# AMU-S11-V00-ContactorInterface.net
KiCad netlist of a schematic drawn in Altium Designer
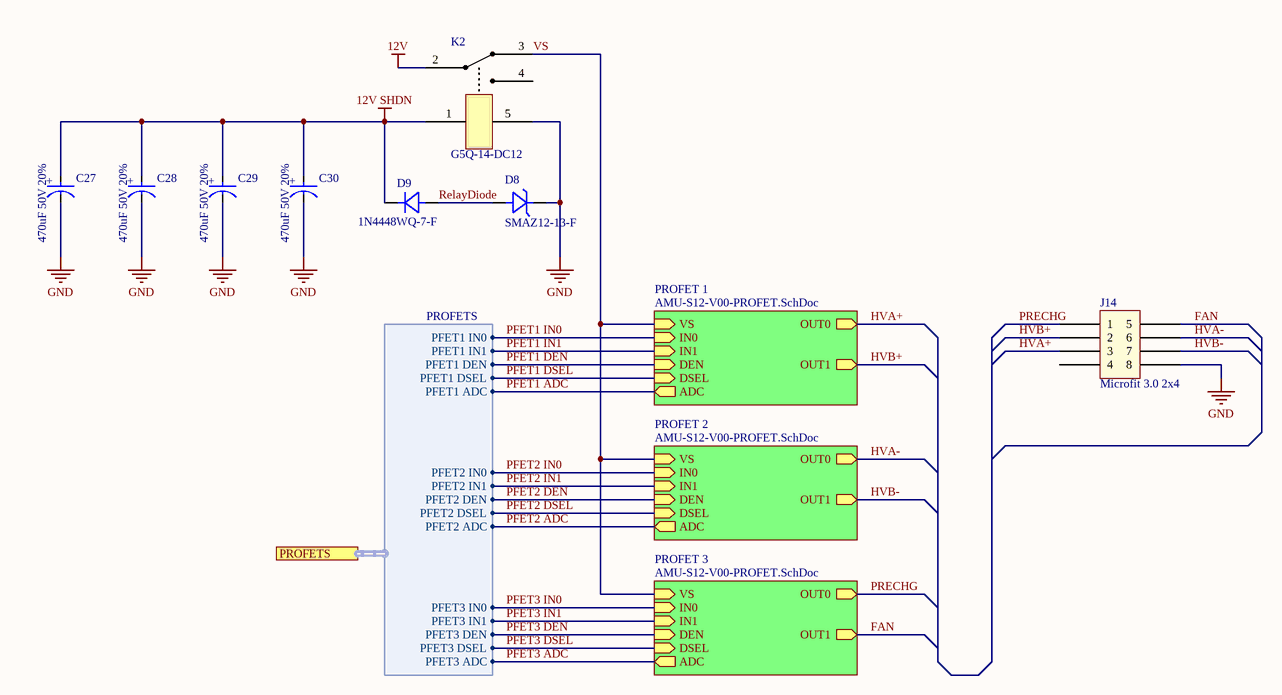
[diagram p0: AMU-S11-V00-ContactorInterface.SchDoc]

(export (version "E")
  (design (tool "Eeschema 10.0.6"))
  (components
    (comp (ref "C27")
      (value "470uF 50V 20%")
      (footprint "CAP_ALU_TH")
      (description "470µF 50V Aluminum Electrolytic Capacitors Radial, Can  5000 Hrs @ 105°C")
      (libsource (lib "StandardCapacitors") (part "470uF 50V 20% Alum E-CAP"))
    )
    (comp (ref "C28")
      (value "470uF 50V 20%")
      (footprint "CAP_ALU_TH")
      (description "470µF 50V Aluminum Electrolytic Capacitors Radial, Can  5000 Hrs @ 105°C")
      (libsource (lib "StandardCapacitors") (part "470uF 50V 20% Alum E-CAP"))
    )
    (comp (ref "C29")
      (value "470uF 50V 20%")
      (footprint "CAP_ALU_TH")
      (description "470µF 50V Aluminum Electrolytic Capacitors Radial, Can  5000 Hrs @ 105°C")
      (libsource (lib "StandardCapacitors") (part "470uF 50V 20% Alum E-CAP"))
    )
    (comp (ref "C30")
      (value "470uF 50V 20%")
      (footprint "CAP_ALU_TH")
      (description "470µF 50V Aluminum Electrolytic Capacitors Radial, Can  5000 Hrs @ 105°C")
      (libsource (lib "StandardCapacitors") (part "470uF 50V 20% Alum E-CAP"))
    )
    (comp (ref "D8")
      (value "SMAZ12-13-F")
      (footprint "SMA")
      (description "Zener Diode 12V 1W ±5% Surface Mount SMA")
      (fields (field (name "MANUFACTURER") "ON Semiconductor") (field (name "MPN") "MM3Z56VB"))
      (libsource (lib "QUTMS_DiodeLibrary") (part "SMAZ12-13-F"))
    )
    (comp (ref "D9")
      (value "1N4448WQ-7-F")
      (footprint "SMA")
      (description "Diode, SMD, 75V, 5%, 250mA, SOD123")
      (fields
        (field (name "MANUFACTURER") "ON Semiconductor / Fairchild")
        (field (name "MANUFACTURER PART NUMBER") "1N914BWS")
      )
      (libsource (lib "QUTMS_DiodeLibrary") (part "1N4448WQ-7-F"))
    )
    (comp (ref "J14")
      (value "Microfit 3.0 2x4")
      (footprint "Microfit_2X4_R_TH")
      (libsource (lib "QUTMS_MicrofitLibrary") (part "Microfit_2x4"))
    )
    (comp (ref "K2")
      (value "G5Q-14-DC12")
      (footprint "G5Q-14")
      (description "General Purpose Relay SPDT (1 Form C) 12VDC Coil Through Hole, 12V, 16A")
      (libsource (lib "QUTMS_RelayLibrary") (part "G5Q-14-DC12"))
    )
  )
  (nets
    (net (code "2") (name "/FAN") (class "Default")
      (node (ref "J14") (pin "5") (pinfunction "5_5") (pintype "passive"))
    )
    (net (code "3") (name "/HVA+") (class "Default")
      (node (ref "J14") (pin "3") (pinfunction "3_3") (pintype "passive"))
    )
    (net (code "4") (name "/HVA-") (class "Default")
      (node (ref "J14") (pin "6") (pinfunction "6_6") (pintype "passive"))
    )
    (net (code "5") (name "/HVB+") (class "Default")
      (node (ref "J14") (pin "2") (pinfunction "2_2") (pintype "passive"))
    )
    (net (code "6") (name "/HVB-") (class "Default")
      (node (ref "J14") (pin "7") (pinfunction "7_7") (pintype "passive"))
    )
    (net (code "22") (name "/PRECHG") (class "Default")
      (node (ref "J14") (pin "1") (pinfunction "1_1") (pintype "passive"))
    )
    (net (code "23") (name "/RelayDiode") (class "Default")
      (node (ref "D8") (pin "A") (pinfunction "Anode_A") (pintype "passive"))
      (node (ref "D9") (pin "A") (pinfunction "Anode_A") (pintype "passive"))
    )
    (net (code "24") (name "/VS") (class "Default")
      (node (ref "K2") (pin "3") (pinfunction "3_3") (pintype "passive"))
    )
    (net (code "26") (name "12V") (class "Default")
      (node (ref "K2") (pin "2") (pinfunction "2_2") (pintype "passive"))
    )
    (net (code "27") (name "12V SHDN") (class "Default")
      (node (ref "C27") (pin "A") (pinfunction "A_A") (pintype "passive"))
      (node (ref "C28") (pin "A") (pinfunction "A_A") (pintype "passive"))
      (node (ref "C29") (pin "A") (pinfunction "A_A") (pintype "passive"))
      (node (ref "C30") (pin "A") (pinfunction "A_A") (pintype "passive"))
      (node (ref "D9") (pin "K") (pinfunction "Cathode_K") (pintype "passive"))
      (node (ref "K2") (pin "1") (pinfunction "1_1") (pintype "passive"))
    )
    (net (code "28") (name "GND") (class "Default")
      (node (ref "C27") (pin "K") (pinfunction "K_K") (pintype "passive"))
      (node (ref "C28") (pin "K") (pinfunction "K_K") (pintype "passive"))
      (node (ref "C29") (pin "K") (pinfunction "K_K") (pintype "passive"))
      (node (ref "C30") (pin "K") (pinfunction "K_K") (pintype "passive"))
      (node (ref "D8") (pin "K") (pinfunction "Cathode_K") (pintype "passive"))
      (node (ref "J14") (pin "8") (pinfunction "8_8") (pintype "passive"))
      (node (ref "K2") (pin "5") (pinfunction "5_5") (pintype "passive"))
    )
    (net (code "29") (name "unconnected-(J14-Pad4)") (class "Default")
      (node (ref "J14") (pin "4") (pinfunction "4_4") (pintype "passive"))
    )
    (net (code "30") (name "unconnected-(K2-Pad4)") (class "Default")
      (node (ref "K2") (pin "4") (pinfunction "4_4") (pintype "passive"))
    )
  )
)
